# Lab7SCH.net
KiCad netlist of a schematic drawn in Altium Designer
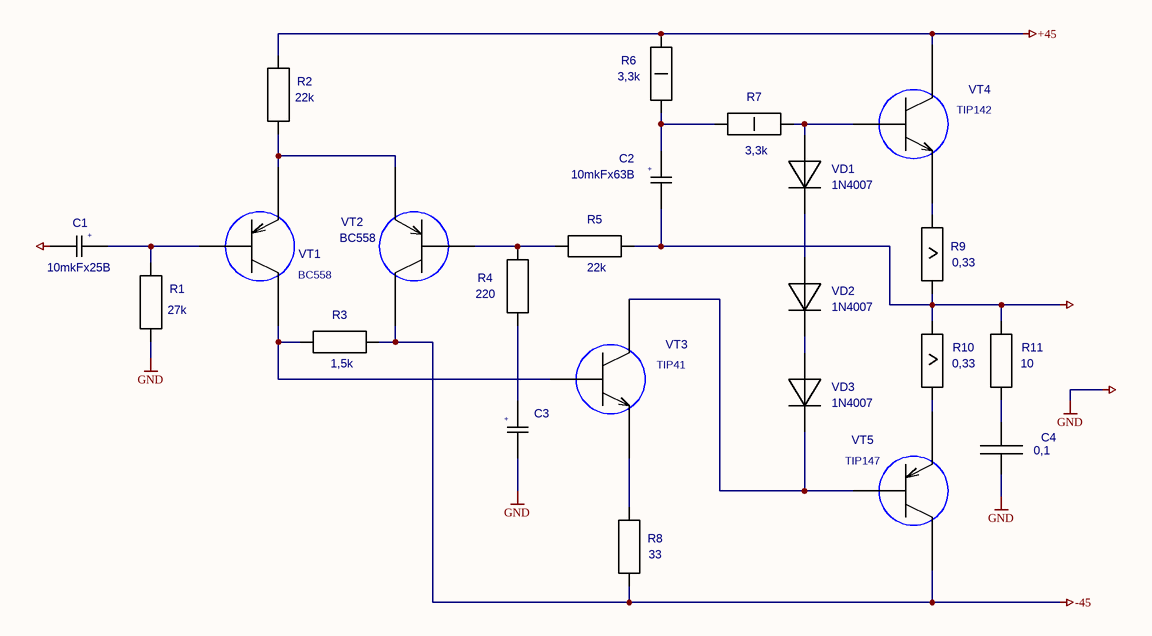
[diagram p0: Lab7SCH.SchDoc]

(export (version "E")
  (design (tool "Eeschema 10.0.6"))
  (components
    (comp (ref "C1")
      (value "10mkFx25B")
      (footprint "K50_29")
      (libsource (lib "Lab_Buhakova") (part "K50_29"))
    )
    (comp (ref "C2")
      (value "10mkFx63B")
      (footprint "K50_29")
      (libsource (lib "Lab_Buhakova") (part "K50_29"))
    )
    (comp (ref "C3") (value "K50_29") (footprint "K50_29") (libsource (lib "Lab_Buhakova") (part "K50_29")))
    (comp (ref "C4")
      (value "0,1")
      (footprint "�10-17�-4")
      (libsource (lib "Kondensator_DIP") (part "�10-17�-�1500-18��"))
    )
    (comp (ref "R1")
      (value "27k")
      (footprint "C2-33H-0.125W")
      (libsource (lib "Resistor_DIP") (part "�2-23-0,125 ��"))
    )
    (comp (ref "R2")
      (value "22k")
      (footprint "C2-33H-0.125W")
      (libsource (lib "Resistor_DIP") (part "�2-23-0,125 ��"))
    )
    (comp (ref "R3")
      (value "1,5k")
      (footprint "C2-33H-0.125W")
      (libsource (lib "Resistor_DIP") (part "�2-23-0,125 ��"))
    )
    (comp (ref "R4")
      (value "220")
      (footprint "C2-33H-0.125W")
      (libsource (lib "Resistor_DIP") (part "�2-23-0,125 ��"))
    )
    (comp (ref "R5")
      (value "22k")
      (footprint "C2-33H-0.125W")
      (libsource (lib "Resistor_DIP") (part "�2-23-0,125 ��"))
    )
    (comp (ref "R6")
      (value "3,3k")
      (footprint "C2-33H-1W_17.5MM")
      (fields (field (name "AUTOR") "pcbdesigner.ru"))
      (libsource (lib "Resistor_DIP") (part "C2-33H-1W_OLD_UGO"))
    )
    (comp (ref "R7")
      (value "3,3k")
      (footprint "C2-33H-1W_17.5MM")
      (fields (field (name "AUTOR") "pcbdesigner.ru"))
      (libsource (lib "Resistor_DIP") (part "C2-33H-1W_OLD_UGO"))
    )
    (comp (ref "R8")
      (value "33")
      (footprint "C2-33H-0.125W")
      (libsource (lib "Resistor_DIP") (part "�2-23-0,125 ��"))
    )
    (comp (ref "R9")
      (value "0,33")
      (footprint "C2-33H-0.5W_15MM")
      (fields (field (name "AUTOR") "pcbdesigner.ru"))
      (libsource (lib "Resistor_DIP") (part "C2-33H-0.5W_OLD_UGO"))
    )
    (comp (ref "R10")
      (value "0,33")
      (footprint "C2-33H-0.5W_15MM")
      (fields (field (name "AUTOR") "pcbdesigner.ru"))
      (libsource (lib "Resistor_DIP") (part "C2-33H-0.5W_OLD_UGO"))
    )
    (comp (ref "R11")
      (value "10")
      (footprint "C2-33H-0.125W")
      (libsource (lib "Resistor_DIP") (part "�2-23-0,125 ��"))
    )
    (comp (ref "VD1")
      (value "1N4007")
      (footprint "DO-41(DO-204AL)_1N4007(Primary)")
      (libsource (lib "Diod") (part "1N4007"))
    )
    (comp (ref "VD2")
      (value "1N4007")
      (footprint "DO-41(DO-204AL)_1N4007(Primary)")
      (libsource (lib "Diod") (part "1N4007"))
    )
    (comp (ref "VD3")
      (value "1N4007")
      (footprint "DO-41(DO-204AL)_1N4007(Primary)")
      (libsource (lib "Diod") (part "1N4007"))
    )
    (comp (ref "VT1") (value "BC558") (footprint "��320�") (libsource (lib "Tranzistor") (part "1�320�_1")))
    (comp (ref "VT2")
      (value "BC558")
      (footprint "2T602A")
      (libsource (lib "Tranzistor") (part "TRANSISTOR_(1111)"))
    )
    (comp (ref "VT3") (value "TIP41") (footprint "��101") (libsource (lib "Tranzistor") (part "��101")))
    (comp (ref "VT4") (value "TIP142") (footprint "��101") (libsource (lib "Tranzistor") (part "��101")))
    (comp (ref "VT5") (value "TIP147") (footprint "��320�") (libsource (lib "Tranzistor") (part "1�320�_1")))
  )
  (nets
    (net (code "1") (name "+45") (class "Default")
      (node (ref "R2") (pin "1") (pinfunction "I/O0_1") (pintype "passive"))
      (node (ref "R6") (pin "2") (pinfunction "2_2") (pintype "passive"))
      (node (ref "VT4") (pin "3") (pinfunction "K_3") (pintype "passive"))
    )
    (net (code "2") (name "-45") (class "Default")
      (node (ref "R3") (pin "2") (pinfunction "I/O1_2") (pintype "passive"))
      (node (ref "R8") (pin "2") (pinfunction "I/O1_2") (pintype "passive"))
      (node (ref "VT2") (pin "1") (pintype "passive"))
      (node (ref "VT5") (pin "2") (pinfunction "K_2") (pintype "passive"))
    )
    (net (code "3") (name "GND") (class "Default")
      (node (ref "C1") (pin "1") (pintype "passive"))
      (node (ref "C2") (pin "1") (pintype "passive"))
      (node (ref "C3") (pin "1") (pintype "passive"))
      (node (ref "C4") (pin "2") (pinfunction "2_2") (pintype "passive"))
      (node (ref "R1") (pin "2") (pinfunction "I/O1_2") (pintype "passive"))
      (node (ref "R10") (pin "1") (pinfunction "1_1") (pintype "passive"))
      (node (ref "R11") (pin "1") (pinfunction "I/O0_1") (pintype "passive"))
      (node (ref "R5") (pin "2") (pinfunction "I/O1_2") (pintype "passive"))
      (node (ref "R9") (pin "2") (pinfunction "2_2") (pintype "passive"))
    )
    (net (code "4") (name "Net-(C2-Pad2)") (class "Default")
      (node (ref "C2") (pin "2") (pintype "passive"))
      (node (ref "R6") (pin "1") (pinfunction "1_1") (pintype "passive"))
      (node (ref "R7") (pin "1") (pinfunction "1_1") (pintype "passive"))
    )
    (net (code "5") (name "Net-(R1-I{slash}O0)") (class "Default")
      (node (ref "C1") (pin "2") (pintype "passive"))
      (node (ref "R1") (pin "1") (pinfunction "I/O0_1") (pintype "passive"))
      (node (ref "VT1") (pin "3") (pinfunction "B_3") (pintype "passive"))
    )
    (net (code "6") (name "Net-(R2-I{slash}O1)") (class "Default")
      (node (ref "R2") (pin "2") (pinfunction "I/O1_2") (pintype "passive"))
      (node (ref "VT1") (pin "1") (pinfunction "E_1") (pintype "passive"))
      (node (ref "VT2") (pin "3") (pintype "passive"))
    )
    (net (code "7") (name "Net-(R3-I{slash}O0)") (class "Default")
      (node (ref "R3") (pin "1") (pinfunction "I/O0_1") (pintype "passive"))
      (node (ref "VT1") (pin "2") (pinfunction "K_2") (pintype "passive"))
      (node (ref "VT3") (pin "2") (pinfunction "B_2") (pintype "passive"))
    )
    (net (code "8") (name "Net-(R4-I{slash}O0)") (class "Default")
      (node (ref "C3") (pin "2") (pintype "passive"))
      (node (ref "R4") (pin "1") (pinfunction "I/O0_1") (pintype "passive"))
    )
    (net (code "9") (name "Net-(R4-I{slash}O1)") (class "Default")
      (node (ref "R4") (pin "2") (pinfunction "I/O1_2") (pintype "passive"))
      (node (ref "R5") (pin "1") (pinfunction "I/O0_1") (pintype "passive"))
      (node (ref "VT2") (pin "2") (pintype "passive"))
    )
    (net (code "10") (name "Net-(R8-I{slash}O0)") (class "Default")
      (node (ref "R8") (pin "1") (pinfunction "I/O0_1") (pintype "passive"))
      (node (ref "VT3") (pin "1") (pinfunction "E_1") (pintype "passive"))
    )
    (net (code "11") (name "Net-(R11-I{slash}O1)") (class "Default")
      (node (ref "C4") (pin "1") (pinfunction "1_1") (pintype "passive"))
      (node (ref "R11") (pin "2") (pinfunction "I/O1_2") (pintype "passive"))
    )
    (net (code "12") (name "Net-(VD1-1)") (class "Default")
      (node (ref "R7") (pin "2") (pinfunction "2_2") (pintype "passive"))
      (node (ref "VD1") (pin "A") (pinfunction "1_A") (pintype "passive"))
      (node (ref "VT4") (pin "2") (pinfunction "B_2") (pintype "passive"))
    )
    (net (code "13") (name "Net-(VD1-2)") (class "Default")
      (node (ref "VD1") (pin "K") (pinfunction "2_K") (pintype "passive"))
      (node (ref "VD2") (pin "A") (pinfunction "1_A") (pintype "passive"))
    )
    (net (code "14") (name "Net-(VD2-2)") (class "Default")
      (node (ref "VD2") (pin "K") (pinfunction "2_K") (pintype "passive"))
      (node (ref "VD3") (pin "A") (pinfunction "1_A") (pintype "passive"))
    )
    (net (code "15") (name "Net-(VD3-2)") (class "Default")
      (node (ref "VD3") (pin "K") (pinfunction "2_K") (pintype "passive"))
      (node (ref "VT3") (pin "3") (pinfunction "K_3") (pintype "passive"))
      (node (ref "VT5") (pin "3") (pinfunction "B_3") (pintype "passive"))
    )
    (net (code "16") (name "Net-(VT4-E)") (class "Default")
      (node (ref "R9") (pin "1") (pinfunction "1_1") (pintype "passive"))
      (node (ref "VT4") (pin "1") (pinfunction "E_1") (pintype "passive"))
    )
    (net (code "17") (name "Net-(VT5-E)") (class "Default")
      (node (ref "R10") (pin "2") (pinfunction "2_2") (pintype "passive"))
      (node (ref "VT5") (pin "1") (pinfunction "E_1") (pintype "passive"))
    )
  )
)
